# Wiring_25112019.net
KiCad netlist of a schematic drawn in EAGLE
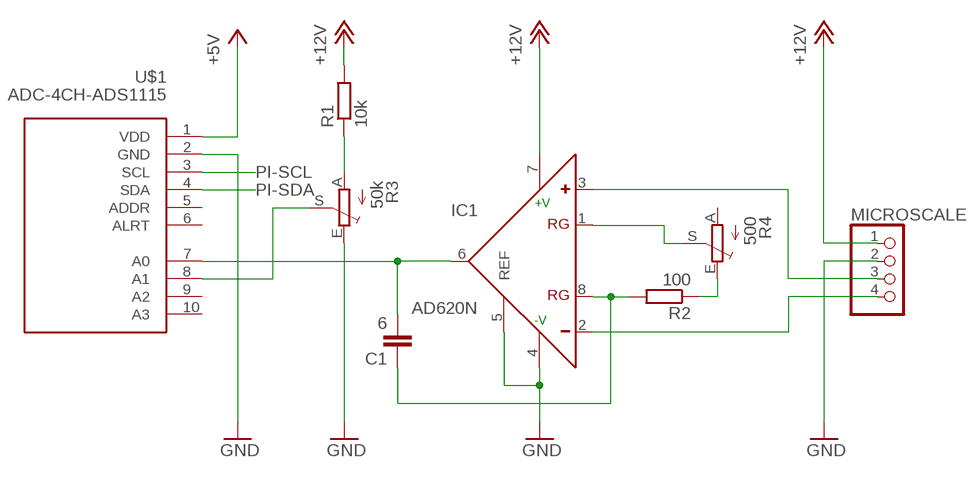
[diagram p0: schematic, sheet 1]

(export (version "E")
  (design (tool "Eeschema 10.0.6"))
  (components
    (comp (ref "C1")
      (value "6")
      (footprint "eagle-import:C025-024X044")
      (libsource (lib "eagle-import") (part "C-EU025-024X044"))
    )
    (comp (ref "IC1")
      (value "AD620N")
      (footprint "eagle-import:DIL08")
      (fields (field (name "MF") "ALTERA CORPORATION") (field (name "MPN") "AD620AN"))
      (libsource (lib "eagle-import") (part "AD620N"))
    )
    (comp (ref "MICROSCALE")
      (value "PINHD-1X4")
      (footprint "eagle-import:1X04")
      (libsource (lib "eagle-import") (part "PINHD-1X4"))
    )
    (comp (ref "R1")
      (value "10k")
      (footprint "eagle-import:0204_5")
      (libsource (lib "eagle-import") (part "R-EU_0204/5"))
    )
    (comp (ref "R2")
      (value "100")
      (footprint "eagle-import:0204_5")
      (libsource (lib "eagle-import") (part "R-EU_0204/5"))
    )
    (comp (ref "R3")
      (value "50k")
      (footprint "eagle-import:LI10")
      (libsource (lib "eagle-import") (part "TRIM_EU-LI10"))
    )
    (comp (ref "R4")
      (value "500")
      (footprint "eagle-import:LI10")
      (libsource (lib "eagle-import") (part "TRIM_EU-LI10"))
    )
    (comp (ref "U$1")
      (value "ADC-4CH-ADS1115")
      (footprint "eagle-import:ADC-4CH-ADS1115")
      (libsource (lib "eagle-import") (part "ADC-4CH-ADS1115"))
    )
  )
  (nets
    (net (code "1") (name "+5V") (class "Default")
      (node (ref "U$1") (pin "1") (pinfunction "VDD_1") (pintype "power_in"))
    )
    (net (code "2") (name "+12V") (class "Default")
      (node (ref "IC1") (pin "7") (pinfunction "+V_7") (pintype "power_in"))
      (node (ref "MICROSCALE") (pin "1") (pinfunction "1_1") (pintype "passive"))
      (node (ref "R1") (pin "2") (pinfunction "2_2") (pintype "passive"))
    )
    (net (code "3") (name "/PI-SCL") (class "Default")
      (node (ref "U$1") (pin "3") (pinfunction "SCL_3") (pintype "bidirectional"))
    )
    (net (code "4") (name "/PI-SDA") (class "Default")
      (node (ref "U$1") (pin "4") (pinfunction "SDA_4") (pintype "bidirectional"))
    )
    (net (code "5") (name "GND") (class "Default")
      (node (ref "IC1") (pin "4") (pinfunction "-V_4") (pintype "power_in"))
      (node (ref "IC1") (pin "5") (pinfunction "REF_5") (pintype "passive"))
      (node (ref "MICROSCALE") (pin "2") (pinfunction "2_2") (pintype "passive"))
      (node (ref "R3") (pin "E") (pinfunction "E_E") (pintype "passive"))
      (node (ref "U$1") (pin "2") (pinfunction "GND_2") (pintype "power_in"))
    )
    (net (code "6") (name "Net-(C1-Pad1)") (class "Default")
      (node (ref "C1") (pin "1") (pinfunction "1_1") (pintype "passive"))
      (node (ref "IC1") (pin "8") (pinfunction "RG_8") (pintype "passive"))
      (node (ref "R2") (pin "2") (pinfunction "2_2") (pintype "passive"))
    )
    (net (code "7") (name "Net-(IC1-+)") (class "Default")
      (node (ref "IC1") (pin "3") (pinfunction "+_3") (pintype "input"))
      (node (ref "MICROSCALE") (pin "3") (pinfunction "3_3") (pintype "passive"))
    )
    (net (code "8") (name "Net-(IC1--)") (class "Default")
      (node (ref "IC1") (pin "2") (pinfunction "-_2") (pintype "input"))
      (node (ref "MICROSCALE") (pin "4") (pinfunction "4_4") (pintype "passive"))
    )
    (net (code "9") (name "Net-(IC1-OUT)") (class "Default")
      (node (ref "C1") (pin "2") (pinfunction "2_2") (pintype "passive"))
      (node (ref "IC1") (pin "6") (pinfunction "OUT_6") (pintype "output"))
      (node (ref "U$1") (pin "7") (pinfunction "A0_7") (pintype "input"))
    )
    (net (code "10") (name "Net-(IC1-RG-Pad1)") (class "Default")
      (node (ref "IC1") (pin "1") (pinfunction "RG_1") (pintype "passive"))
      (node (ref "R4") (pin "S") (pinfunction "S_S") (pintype "passive"))
    )
    (net (code "11") (name "Net-(R1-Pad1)") (class "Default")
      (node (ref "R1") (pin "1") (pinfunction "1_1") (pintype "passive"))
      (node (ref "R3") (pin "A") (pinfunction "A_A") (pintype "passive"))
    )
    (net (code "12") (name "Net-(R2-Pad1)") (class "Default")
      (node (ref "R2") (pin "1") (pinfunction "1_1") (pintype "passive"))
      (node (ref "R4") (pin "E") (pinfunction "E_E") (pintype "passive"))
    )
    (net (code "13") (name "Net-(U$1-A1)") (class "Default")
      (node (ref "R3") (pin "S") (pinfunction "S_S") (pintype "passive"))
      (node (ref "U$1") (pin "8") (pinfunction "A1_8") (pintype "input"))
    )
    (net (code "14") (name "unconnected-(R4-PadA)") (class "Default")
      (node (ref "R4") (pin "A") (pinfunction "A_A") (pintype "passive"))
    )
    (net (code "15") (name "unconnected-(U$1-A2-Pad9)") (class "Default")
      (node (ref "U$1") (pin "9") (pinfunction "A2_9") (pintype "input"))
    )
    (net (code "16") (name "unconnected-(U$1-A3-Pad10)") (class "Default")
      (node (ref "U$1") (pin "10") (pinfunction "A3_10") (pintype "input"))
    )
    (net (code "17") (name "unconnected-(U$1-ADDR-Pad5)") (class "Default")
      (node (ref "U$1") (pin "5") (pinfunction "ADDR_5") (pintype "bidirectional"))
    )
    (net (code "18") (name "unconnected-(U$1-ALRT-Pad6)") (class "Default")
      (node (ref "U$1") (pin "6") (pinfunction "ALRT_6") (pintype "bidirectional"))
    )
  )
)
